# MC3446_E7.net
KiCad netlist of a schematic drawn in EAGLE
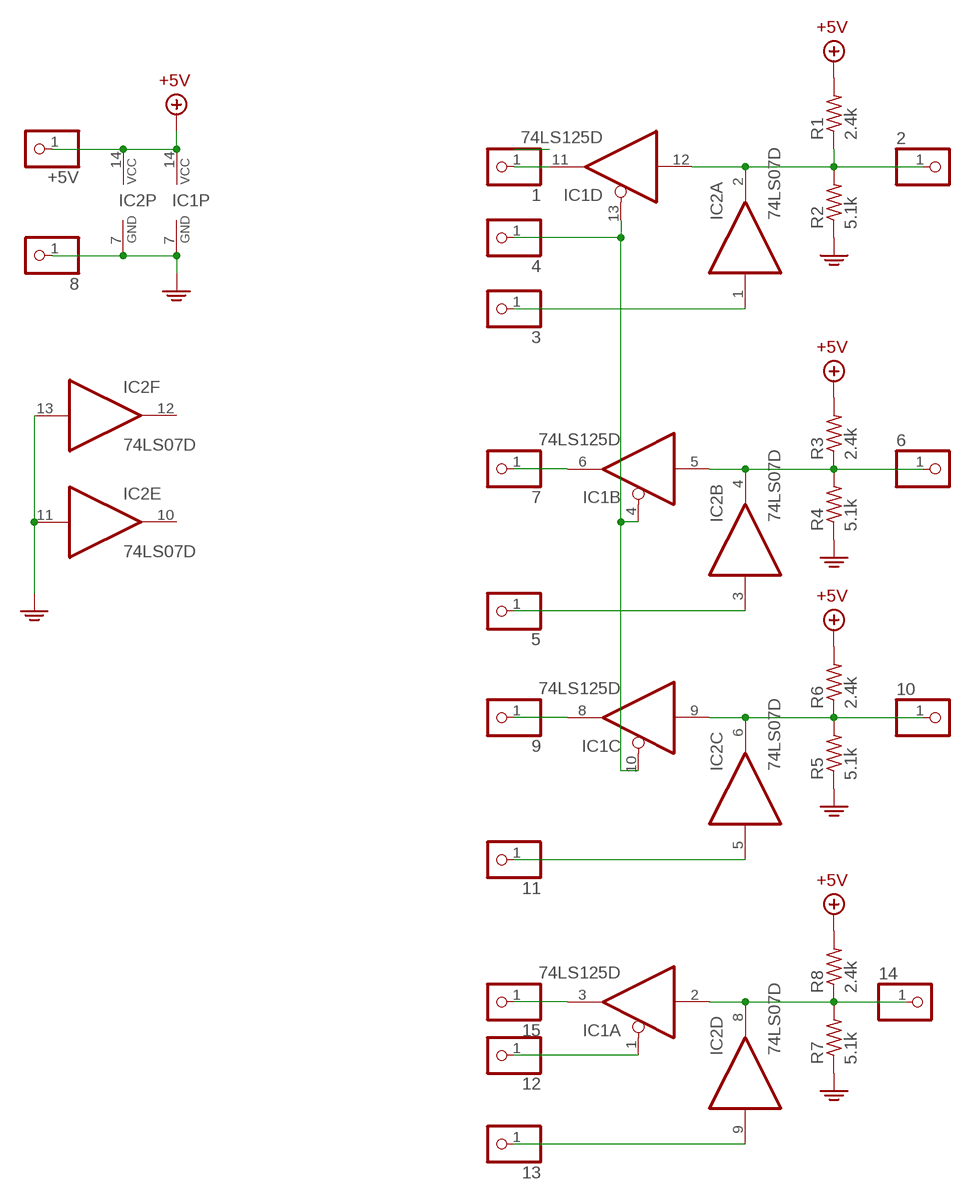
[diagram p0: schematic, sheet 1]

(export (version "E")
  (design (tool "Eeschema 10.0.6"))
  (components
    (comp (ref "+5V")
      (value "PINHD-1X1")
      (footprint "eagle-import:1X01")
      (libsource (lib "eagle-import") (part "PINHD-1X1"))
    )
    (comp (ref "1")
      (value "PINHD-1X1")
      (footprint "eagle-import:1X01")
      (libsource (lib "eagle-import") (part "PINHD-1X1"))
    )
    (comp (ref "2")
      (value "PINHD-1X1")
      (footprint "eagle-import:1X01")
      (libsource (lib "eagle-import") (part "PINHD-1X1"))
    )
    (comp (ref "3")
      (value "PINHD-1X1")
      (footprint "eagle-import:1X01")
      (libsource (lib "eagle-import") (part "PINHD-1X1"))
    )
    (comp (ref "4")
      (value "PINHD-1X1")
      (footprint "eagle-import:1X01")
      (libsource (lib "eagle-import") (part "PINHD-1X1"))
    )
    (comp (ref "5")
      (value "PINHD-1X1")
      (footprint "eagle-import:1X01")
      (libsource (lib "eagle-import") (part "PINHD-1X1"))
    )
    (comp (ref "6")
      (value "PINHD-1X1")
      (footprint "eagle-import:1X01")
      (libsource (lib "eagle-import") (part "PINHD-1X1"))
    )
    (comp (ref "7")
      (value "PINHD-1X1")
      (footprint "eagle-import:1X01")
      (libsource (lib "eagle-import") (part "PINHD-1X1"))
    )
    (comp (ref "8")
      (value "PINHD-1X1")
      (footprint "eagle-import:1X01")
      (libsource (lib "eagle-import") (part "PINHD-1X1"))
    )
    (comp (ref "9")
      (value "PINHD-1X1")
      (footprint "eagle-import:1X01")
      (libsource (lib "eagle-import") (part "PINHD-1X1"))
    )
    (comp (ref "10")
      (value "PINHD-1X1")
      (footprint "eagle-import:1X01")
      (libsource (lib "eagle-import") (part "PINHD-1X1"))
    )
    (comp (ref "11")
      (value "PINHD-1X1")
      (footprint "eagle-import:1X01")
      (libsource (lib "eagle-import") (part "PINHD-1X1"))
    )
    (comp (ref "12")
      (value "PINHD-1X1")
      (footprint "eagle-import:1X01")
      (libsource (lib "eagle-import") (part "PINHD-1X1"))
    )
    (comp (ref "13")
      (value "PINHD-1X1")
      (footprint "eagle-import:1X01")
      (libsource (lib "eagle-import") (part "PINHD-1X1"))
    )
    (comp (ref "14")
      (value "PINHD-1X1")
      (footprint "eagle-import:1X01")
      (libsource (lib "eagle-import") (part "PINHD-1X1"))
    )
    (comp (ref "15")
      (value "PINHD-1X1")
      (footprint "eagle-import:1X01")
      (libsource (lib "eagle-import") (part "PINHD-1X1"))
    )
    (comp (ref "IC1")
      (value "74LS125D")
      (footprint "eagle-import:SO14")
      (libsource (lib "eagle-import") (part "74125DLS"))
    )
    (comp (ref "IC2")
      (value "74LS07D")
      (footprint "eagle-import:SO14")
      (libsource (lib "eagle-import") (part "7407DLS"))
    )
    (comp (ref "R1")
      (value "2.4k")
      (footprint "eagle-import:R0805")
      (libsource (lib "eagle-import") (part "R-US_R0805"))
    )
    (comp (ref "R2")
      (value "5.1k")
      (footprint "eagle-import:R0805")
      (libsource (lib "eagle-import") (part "R-US_R0805"))
    )
    (comp (ref "R3")
      (value "2.4k")
      (footprint "eagle-import:R0805")
      (libsource (lib "eagle-import") (part "R-US_R0805"))
    )
    (comp (ref "R4")
      (value "5.1k")
      (footprint "eagle-import:R0805")
      (libsource (lib "eagle-import") (part "R-US_R0805"))
    )
    (comp (ref "R5")
      (value "5.1k")
      (footprint "eagle-import:R0805")
      (libsource (lib "eagle-import") (part "R-US_R0805"))
    )
    (comp (ref "R6")
      (value "2.4k")
      (footprint "eagle-import:R0805")
      (libsource (lib "eagle-import") (part "R-US_R0805"))
    )
    (comp (ref "R7")
      (value "5.1k")
      (footprint "eagle-import:R0805")
      (libsource (lib "eagle-import") (part "R-US_R0805"))
    )
    (comp (ref "R8")
      (value "2.4k")
      (footprint "eagle-import:R0805")
      (libsource (lib "eagle-import") (part "R-US_R0805"))
    )
  )
  (nets
    (net (code "1") (name "+5V") (class "Default")
      (node (ref "+5V") (pin "1") (pinfunction "1_1") (pintype "passive"))
      (node (ref "IC1") (pin "14") (pinfunction "VCC_14") (pintype "power_in"))
      (node (ref "IC2") (pin "14") (pinfunction "VCC_14") (pintype "power_in"))
      (node (ref "R1") (pin "2") (pinfunction "2_2") (pintype "passive"))
      (node (ref "R3") (pin "2") (pinfunction "2_2") (pintype "passive"))
      (node (ref "R6") (pin "2") (pinfunction "2_2") (pintype "passive"))
      (node (ref "R8") (pin "2") (pinfunction "2_2") (pintype "passive"))
    )
    (net (code "2") (name "GND") (class "Default")
      (node (ref "8") (pin "1") (pinfunction "1_1") (pintype "passive"))
      (node (ref "IC1") (pin "7") (pinfunction "GND_7") (pintype "power_in"))
      (node (ref "IC2") (pin "11") (pinfunction "I_11") (pintype "input"))
      (node (ref "IC2") (pin "13") (pinfunction "I_13") (pintype "input"))
      (node (ref "IC2") (pin "7") (pinfunction "GND_7") (pintype "power_in"))
      (node (ref "R2") (pin "1") (pinfunction "1_1") (pintype "passive"))
      (node (ref "R4") (pin "1") (pinfunction "1_1") (pintype "passive"))
      (node (ref "R5") (pin "1") (pinfunction "1_1") (pintype "passive"))
      (node (ref "R7") (pin "1") (pinfunction "1_1") (pintype "passive"))
    )
    (net (code "3") (name "Net-(IC1A-I)") (class "Default")
      (node (ref "14") (pin "1") (pinfunction "1_1") (pintype "passive"))
      (node (ref "IC1") (pin "2") (pinfunction "I_2") (pintype "input"))
      (node (ref "IC2") (pin "8") (pinfunction "O_8") (pintype "open_collector"))
      (node (ref "R7") (pin "2") (pinfunction "2_2") (pintype "passive"))
      (node (ref "R8") (pin "1") (pinfunction "1_1") (pintype "passive"))
    )
    (net (code "4") (name "Net-(IC1A-O)") (class "Default")
      (node (ref "15") (pin "1") (pinfunction "1_1") (pintype "passive"))
      (node (ref "IC1") (pin "3") (pinfunction "O_3") (pintype "tri_state"))
    )
    (net (code "5") (name "Net-(IC1A-OE)") (class "Default")
      (node (ref "12") (pin "1") (pinfunction "1_1") (pintype "passive"))
      (node (ref "IC1") (pin "1") (pinfunction "OE_1") (pintype "input"))
    )
    (net (code "6") (name "Net-(IC1B-I)") (class "Default")
      (node (ref "6") (pin "1") (pinfunction "1_1") (pintype "passive"))
      (node (ref "IC1") (pin "5") (pinfunction "I_5") (pintype "input"))
      (node (ref "IC2") (pin "4") (pinfunction "O_4") (pintype "open_collector"))
      (node (ref "R3") (pin "1") (pinfunction "1_1") (pintype "passive"))
      (node (ref "R4") (pin "2") (pinfunction "2_2") (pintype "passive"))
    )
    (net (code "7") (name "Net-(IC1B-O)") (class "Default")
      (node (ref "7") (pin "1") (pinfunction "1_1") (pintype "passive"))
      (node (ref "IC1") (pin "6") (pinfunction "O_6") (pintype "tri_state"))
    )
    (net (code "8") (name "Net-(IC1B-OE)") (class "Default")
      (node (ref "4") (pin "1") (pinfunction "1_1") (pintype "passive"))
      (node (ref "IC1") (pin "10") (pinfunction "OE_10") (pintype "input"))
      (node (ref "IC1") (pin "13") (pinfunction "OE_13") (pintype "input"))
      (node (ref "IC1") (pin "4") (pinfunction "OE_4") (pintype "input"))
    )
    (net (code "9") (name "Net-(IC1C-I)") (class "Default")
      (node (ref "10") (pin "1") (pinfunction "1_1") (pintype "passive"))
      (node (ref "IC1") (pin "9") (pinfunction "I_9") (pintype "input"))
      (node (ref "IC2") (pin "6") (pinfunction "O_6") (pintype "open_collector"))
      (node (ref "R5") (pin "2") (pinfunction "2_2") (pintype "passive"))
      (node (ref "R6") (pin "1") (pinfunction "1_1") (pintype "passive"))
    )
    (net (code "10") (name "Net-(IC1C-O)") (class "Default")
      (node (ref "9") (pin "1") (pinfunction "1_1") (pintype "passive"))
      (node (ref "IC1") (pin "8") (pinfunction "O_8") (pintype "tri_state"))
    )
    (net (code "11") (name "Net-(IC1D-I)") (class "Default")
      (node (ref "2") (pin "1") (pinfunction "1_1") (pintype "passive"))
      (node (ref "IC1") (pin "12") (pinfunction "I_12") (pintype "input"))
      (node (ref "IC2") (pin "2") (pinfunction "O_2") (pintype "open_collector"))
      (node (ref "R1") (pin "1") (pinfunction "1_1") (pintype "passive"))
      (node (ref "R2") (pin "2") (pinfunction "2_2") (pintype "passive"))
    )
    (net (code "12") (name "Net-(IC1D-O)") (class "Default")
      (node (ref "1") (pin "1") (pinfunction "1_1") (pintype "passive"))
      (node (ref "IC1") (pin "11") (pinfunction "O_11") (pintype "tri_state"))
    )
    (net (code "13") (name "Net-(IC2A-I)") (class "Default")
      (node (ref "3") (pin "1") (pinfunction "1_1") (pintype "passive"))
      (node (ref "IC2") (pin "1") (pinfunction "I_1") (pintype "input"))
    )
    (net (code "14") (name "Net-(IC2B-I)") (class "Default")
      (node (ref "5") (pin "1") (pinfunction "1_1") (pintype "passive"))
      (node (ref "IC2") (pin "3") (pinfunction "I_3") (pintype "input"))
    )
    (net (code "15") (name "Net-(IC2C-I)") (class "Default")
      (node (ref "11") (pin "1") (pinfunction "1_1") (pintype "passive"))
      (node (ref "IC2") (pin "5") (pinfunction "I_5") (pintype "input"))
    )
    (net (code "16") (name "Net-(IC2D-I)") (class "Default")
      (node (ref "13") (pin "1") (pinfunction "1_1") (pintype "passive"))
      (node (ref "IC2") (pin "9") (pinfunction "I_9") (pintype "input"))
    )
    (net (code "17") (name "unconnected-(IC2E-O-Pad10)") (class "Default")
      (node (ref "IC2") (pin "10") (pinfunction "O_10") (pintype "open_collector"))
    )
    (net (code "18") (name "unconnected-(IC2F-O-Pad12)") (class "Default")
      (node (ref "IC2") (pin "12") (pinfunction "O_12") (pintype "open_collector"))
    )
  )
)
